# day0_Mukhtar_Amin_13214123.net
KiCad netlist of a schematic drawn in EAGLE
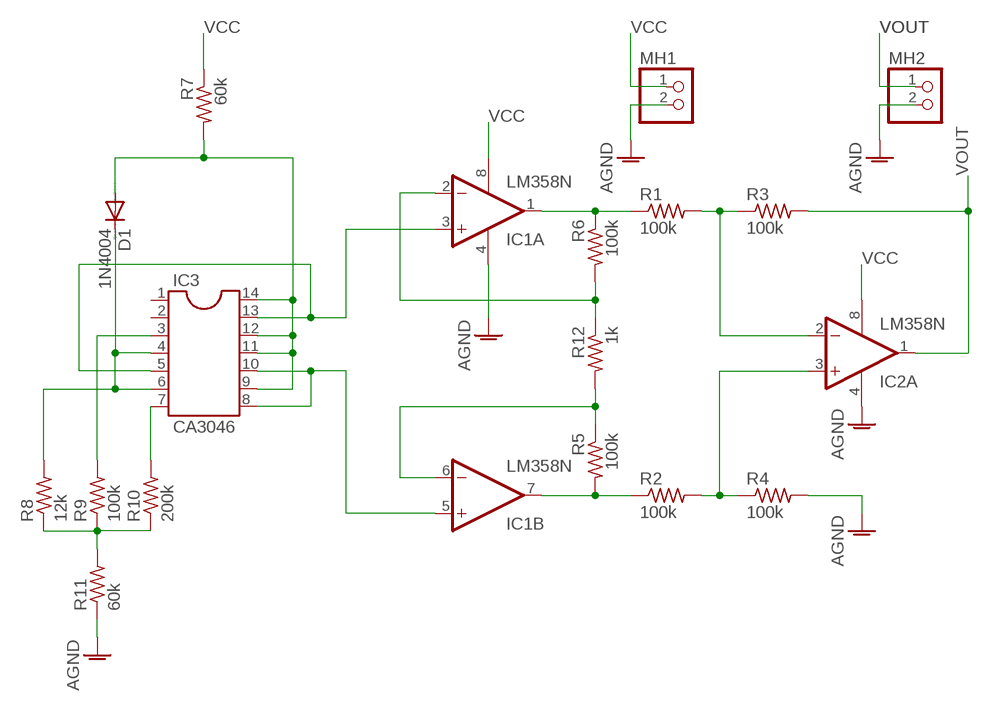
[diagram p0: schematic, sheet 1]

(export (version "E")
  (design (tool "Eeschema 10.0.6"))
  (components
    (comp (ref "D1")
      (value "1N4004")
      (footprint "eagle-import:DO41-10")
      (libsource (lib "eagle-import") (part "1N4004"))
    )
    (comp (ref "IC1")
      (value "LM358N")
      (footprint "eagle-import:DIL08")
      (libsource (lib "eagle-import") (part "LM358N"))
    )
    (comp (ref "IC2")
      (value "LM358N")
      (footprint "eagle-import:DIL08")
      (libsource (lib "eagle-import") (part "LM358N"))
    )
    (comp (ref "IC3")
      (value "CA3046")
      (footprint "eagle-import:DIL14")
      (libsource (lib "eagle-import") (part "DIL14"))
    )
    (comp (ref "MH1")
      (value "PINHD-1X2")
      (footprint "eagle-import:1X02")
      (libsource (lib "eagle-import") (part "PINHD-1X2"))
    )
    (comp (ref "MH2")
      (value "PINHD-1X2")
      (footprint "eagle-import:1X02")
      (libsource (lib "eagle-import") (part "PINHD-1X2"))
    )
    (comp (ref "R1")
      (value "100k")
      (footprint "eagle-import:0204_7")
      (libsource (lib "eagle-import") (part "R-US_0204/7"))
    )
    (comp (ref "R2")
      (value "100k")
      (footprint "eagle-import:0204_7")
      (libsource (lib "eagle-import") (part "R-US_0204/7"))
    )
    (comp (ref "R3")
      (value "100k")
      (footprint "eagle-import:0204_7")
      (libsource (lib "eagle-import") (part "R-US_0204/7"))
    )
    (comp (ref "R4")
      (value "100k")
      (footprint "eagle-import:0204_7")
      (libsource (lib "eagle-import") (part "R-US_0204/7"))
    )
    (comp (ref "R5")
      (value "100k")
      (footprint "eagle-import:0204_7")
      (libsource (lib "eagle-import") (part "R-US_0204/7"))
    )
    (comp (ref "R6")
      (value "100k")
      (footprint "eagle-import:0204_7")
      (libsource (lib "eagle-import") (part "R-US_0204/7"))
    )
    (comp (ref "R7")
      (value "60k")
      (footprint "eagle-import:0204_7")
      (libsource (lib "eagle-import") (part "R-US_0204/7"))
    )
    (comp (ref "R8")
      (value "12k")
      (footprint "eagle-import:0204_7")
      (libsource (lib "eagle-import") (part "R-US_0204/7"))
    )
    (comp (ref "R9")
      (value "100k")
      (footprint "eagle-import:0204_7")
      (libsource (lib "eagle-import") (part "R-US_0204/7"))
    )
    (comp (ref "R10")
      (value "200k")
      (footprint "eagle-import:0204_7")
      (libsource (lib "eagle-import") (part "R-US_0204/7"))
    )
    (comp (ref "R11")
      (value "60k")
      (footprint "eagle-import:0204_7")
      (libsource (lib "eagle-import") (part "R-US_0204/7"))
    )
    (comp (ref "R12")
      (value "1k")
      (footprint "eagle-import:0204_7")
      (libsource (lib "eagle-import") (part "R-US_0204/7"))
    )
  )
  (nets
    (net (code "1") (name "/VCC") (class "Default")
      (node (ref "IC1") (pin "8") (pinfunction "V+_8") (pintype "power_in"))
      (node (ref "IC2") (pin "8") (pinfunction "V+_8") (pintype "power_in"))
      (node (ref "MH1") (pin "1") (pinfunction "1_1") (pintype "passive"))
      (node (ref "R7") (pin "1") (pinfunction "1_1") (pintype "passive"))
    )
    (net (code "2") (name "/VOUT") (class "Default")
      (node (ref "IC2") (pin "1") (pinfunction "OUT_1") (pintype "output"))
      (node (ref "MH2") (pin "1") (pinfunction "1_1") (pintype "passive"))
      (node (ref "R3") (pin "2") (pinfunction "2_2") (pintype "passive"))
    )
    (net (code "3") (name "AGND") (class "Default")
      (node (ref "IC1") (pin "4") (pinfunction "V-_4") (pintype "power_in"))
      (node (ref "IC2") (pin "4") (pinfunction "V-_4") (pintype "power_in"))
      (node (ref "MH1") (pin "2") (pinfunction "2_2") (pintype "passive"))
      (node (ref "MH2") (pin "2") (pinfunction "2_2") (pintype "passive"))
      (node (ref "R11") (pin "1") (pinfunction "1_1") (pintype "passive"))
      (node (ref "R4") (pin "2") (pinfunction "2_2") (pintype "passive"))
    )
    (net (code "4") (name "Net-(D1-PadA)") (class "Default")
      (node (ref "D1") (pin "A") (pinfunction "A_A") (pintype "passive"))
      (node (ref "IC3") (pin "11") (pinfunction "11_11") (pintype "passive"))
      (node (ref "IC3") (pin "12") (pinfunction "12_12") (pintype "passive"))
      (node (ref "IC3") (pin "14") (pinfunction "14_14") (pintype "passive"))
      (node (ref "IC3") (pin "9") (pinfunction "9_9") (pintype "passive"))
      (node (ref "R7") (pin "2") (pinfunction "2_2") (pintype "passive"))
    )
    (net (code "5") (name "Net-(D1-PadC)") (class "Default")
      (node (ref "D1") (pin "C") (pinfunction "C_C") (pintype "passive"))
      (node (ref "IC3") (pin "4") (pinfunction "4_4") (pintype "passive"))
      (node (ref "IC3") (pin "6") (pinfunction "6_6") (pintype "passive"))
      (node (ref "R8") (pin "2") (pinfunction "2_2") (pintype "passive"))
    )
    (net (code "6") (name "Net-(IC1A-+IN)") (class "Default")
      (node (ref "IC1") (pin "3") (pinfunction "+IN_3") (pintype "input"))
      (node (ref "IC3") (pin "13") (pinfunction "13_13") (pintype "passive"))
      (node (ref "IC3") (pin "5") (pinfunction "5_5") (pintype "passive"))
    )
    (net (code "7") (name "Net-(IC1A--IN)") (class "Default")
      (node (ref "IC1") (pin "2") (pinfunction "-IN_2") (pintype "input"))
      (node (ref "R12") (pin "1") (pinfunction "1_1") (pintype "passive"))
      (node (ref "R6") (pin "2") (pinfunction "2_2") (pintype "passive"))
    )
    (net (code "8") (name "Net-(IC1A-OUT)") (class "Default")
      (node (ref "IC1") (pin "1") (pinfunction "OUT_1") (pintype "output"))
      (node (ref "R1") (pin "1") (pinfunction "1_1") (pintype "passive"))
      (node (ref "R6") (pin "1") (pinfunction "1_1") (pintype "passive"))
    )
    (net (code "9") (name "Net-(IC1B-+IN)") (class "Default")
      (node (ref "IC1") (pin "5") (pinfunction "+IN_5") (pintype "input"))
      (node (ref "IC3") (pin "10") (pinfunction "10_10") (pintype "passive"))
      (node (ref "IC3") (pin "8") (pinfunction "8_8") (pintype "passive"))
    )
    (net (code "10") (name "Net-(IC1B--IN)") (class "Default")
      (node (ref "IC1") (pin "6") (pinfunction "-IN_6") (pintype "input"))
      (node (ref "R12") (pin "2") (pinfunction "2_2") (pintype "passive"))
      (node (ref "R5") (pin "1") (pinfunction "1_1") (pintype "passive"))
    )
    (net (code "11") (name "Net-(IC1B-OUT)") (class "Default")
      (node (ref "IC1") (pin "7") (pinfunction "OUT_7") (pintype "output"))
      (node (ref "R2") (pin "1") (pinfunction "1_1") (pintype "passive"))
      (node (ref "R5") (pin "2") (pinfunction "2_2") (pintype "passive"))
    )
    (net (code "12") (name "Net-(IC2A-+IN)") (class "Default")
      (node (ref "IC2") (pin "3") (pinfunction "+IN_3") (pintype "input"))
      (node (ref "R2") (pin "2") (pinfunction "2_2") (pintype "passive"))
      (node (ref "R4") (pin "1") (pinfunction "1_1") (pintype "passive"))
    )
    (net (code "13") (name "Net-(IC2A--IN)") (class "Default")
      (node (ref "IC2") (pin "2") (pinfunction "-IN_2") (pintype "input"))
      (node (ref "R1") (pin "2") (pinfunction "2_2") (pintype "passive"))
      (node (ref "R3") (pin "1") (pinfunction "1_1") (pintype "passive"))
    )
    (net (code "14") (name "Net-(IC3-Pad3)") (class "Default")
      (node (ref "IC3") (pin "3") (pinfunction "3_3") (pintype "passive"))
      (node (ref "R9") (pin "2") (pinfunction "2_2") (pintype "passive"))
    )
    (net (code "15") (name "Net-(IC3-Pad7)") (class "Default")
      (node (ref "IC3") (pin "7") (pinfunction "7_7") (pintype "passive"))
      (node (ref "R10") (pin "2") (pinfunction "2_2") (pintype "passive"))
    )
    (net (code "16") (name "Net-(R10-Pad1)") (class "Default")
      (node (ref "R10") (pin "1") (pinfunction "1_1") (pintype "passive"))
      (node (ref "R11") (pin "2") (pinfunction "2_2") (pintype "passive"))
      (node (ref "R8") (pin "1") (pinfunction "1_1") (pintype "passive"))
      (node (ref "R9") (pin "1") (pinfunction "1_1") (pintype "passive"))
    )
    (net (code "17") (name "unconnected-(IC3-Pad1)") (class "Default")
      (node (ref "IC3") (pin "1") (pinfunction "1_1") (pintype "passive"))
    )
    (net (code "18") (name "unconnected-(IC3-Pad2)") (class "Default")
      (node (ref "IC3") (pin "2") (pinfunction "2_2") (pintype "passive"))
    )
  )
)
